# PLT-01-RevC.net
KiCad netlist of a schematic drawn in EAGLE
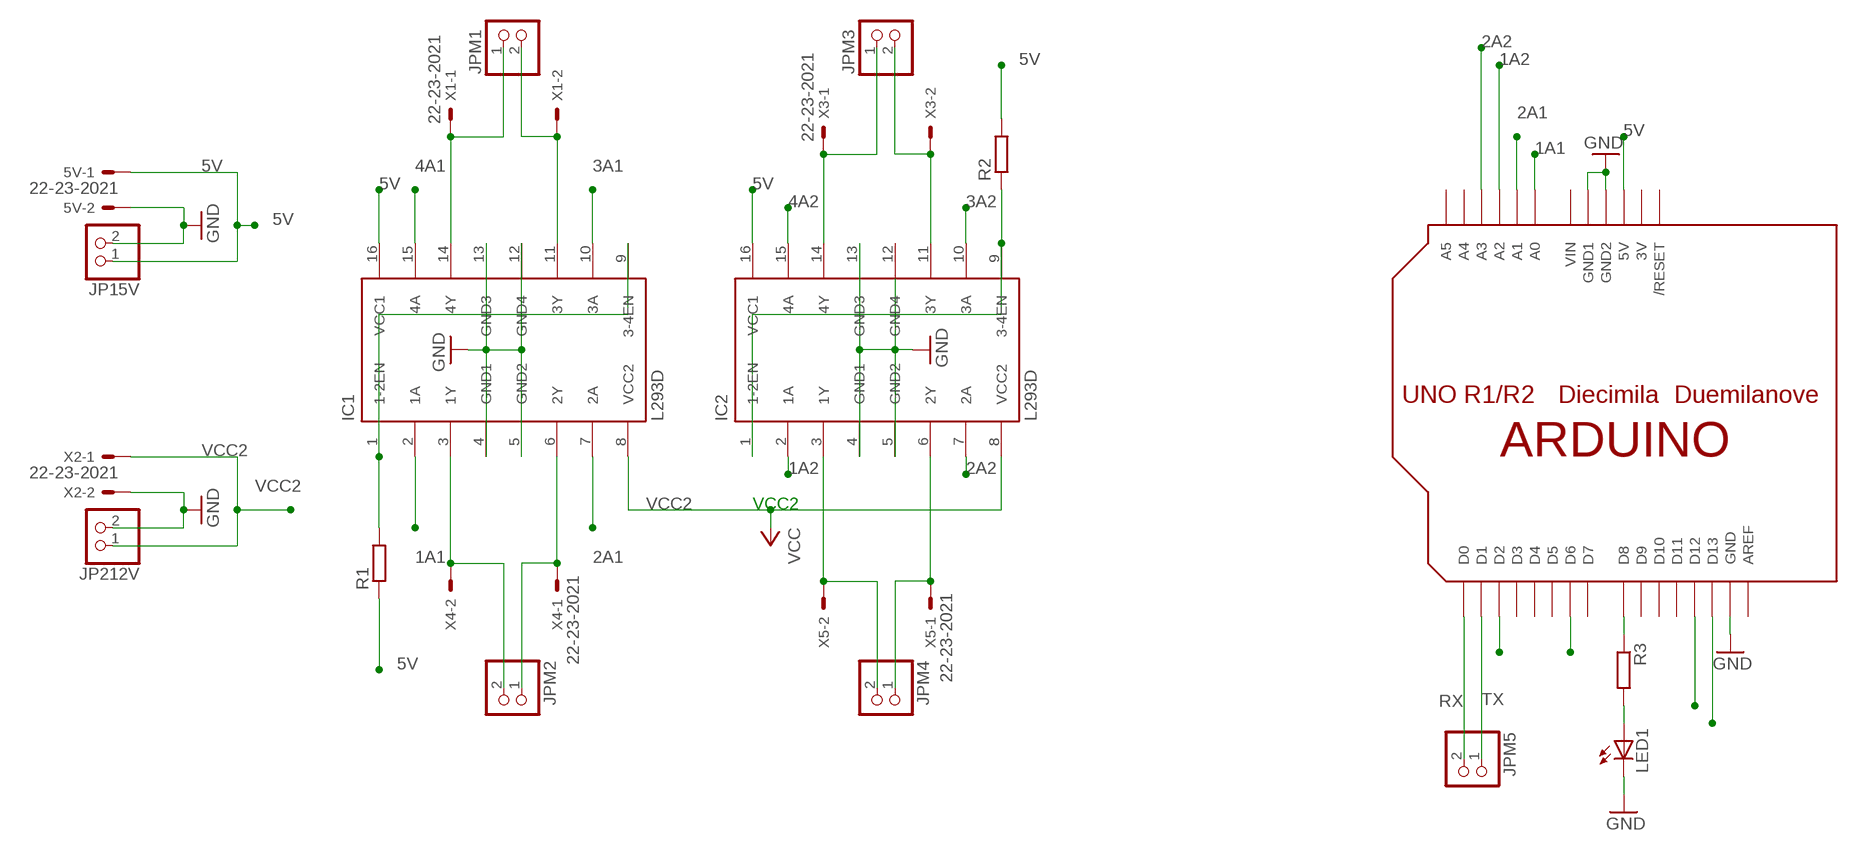
[diagram p0: schematic, sheet 1]

(export (version "E")
  (design (tool "Eeschema 10.0.6"))
  (components
    (comp (ref "5V")
      (value "22-23-2021")
      (footprint "eagle-import:22-23-2021")
      (fields (field (name "MF") "MOLEX"))
      (libsource (lib "eagle-import") (part "22-23-2021"))
    )
    (comp (ref "IC1")
      (value "L293D")
      (footprint "eagle-import:DIL16")
      (libsource (lib "eagle-import") (part "L293D"))
    )
    (comp (ref "IC2")
      (value "L293D")
      (footprint "eagle-import:DIL16")
      (libsource (lib "eagle-import") (part "L293D"))
    )
    (comp (ref "JP15V")
      (value "PINHD-1X2")
      (footprint "eagle-import:1X02")
      (libsource (lib "eagle-import") (part "PINHD-1X2"))
    )
    (comp (ref "JP212V")
      (value "PINHD-1X2")
      (footprint "eagle-import:1X02")
      (libsource (lib "eagle-import") (part "PINHD-1X2"))
    )
    (comp (ref "JPM1")
      (value "PINHD-1X2")
      (footprint "eagle-import:1X02")
      (libsource (lib "eagle-import") (part "PINHD-1X2"))
    )
    (comp (ref "JPM2")
      (value "PINHD-1X2")
      (footprint "eagle-import:1X02")
      (libsource (lib "eagle-import") (part "PINHD-1X2"))
    )
    (comp (ref "JPM3")
      (value "PINHD-1X2")
      (footprint "eagle-import:1X02")
      (libsource (lib "eagle-import") (part "PINHD-1X2"))
    )
    (comp (ref "JPM4")
      (value "PINHD-1X2")
      (footprint "eagle-import:1X02")
      (libsource (lib "eagle-import") (part "PINHD-1X2"))
    )
    (comp (ref "JPM5")
      (value "PINHD-1X2")
      (footprint "eagle-import:1X02")
      (libsource (lib "eagle-import") (part "PINHD-1X2"))
    )
    (comp (ref "LED1")
      (value "LED5MM")
      (footprint "eagle-import:LED5MM")
      (libsource (lib "eagle-import") (part "LED5MM"))
    )
    (comp (ref "R1")
      (value "R-EU_0207/10")
      (footprint "eagle-import:0207_10")
      (libsource (lib "eagle-import") (part "R-EU_0207/10"))
    )
    (comp (ref "R2")
      (value "R-EU_0207/10")
      (footprint "eagle-import:0207_10")
      (libsource (lib "eagle-import") (part "R-EU_0207/10"))
    )
    (comp (ref "R3")
      (value "R-EU_0207/10")
      (footprint "eagle-import:0207_10")
      (libsource (lib "eagle-import") (part "R-EU_0207/10"))
    )
    (comp (ref "U$1")
      (value "ARDUINOUNO")
      (footprint "eagle-import:ARDUINO")
      (libsource (lib "eagle-import") (part "ARDUINOUNO"))
    )
    (comp (ref "X1")
      (value "22-23-2021")
      (footprint "eagle-import:22-23-2021")
      (fields (field (name "MF") "MOLEX"))
      (libsource (lib "eagle-import") (part "22-23-2021"))
    )
    (comp (ref "X2")
      (value "22-23-2021")
      (footprint "eagle-import:22-23-2021")
      (fields (field (name "MF") "MOLEX"))
      (libsource (lib "eagle-import") (part "22-23-2021"))
    )
    (comp (ref "X3")
      (value "22-23-2021")
      (footprint "eagle-import:22-23-2021")
      (fields (field (name "MF") "MOLEX"))
      (libsource (lib "eagle-import") (part "22-23-2021"))
    )
    (comp (ref "X4")
      (value "22-23-2021")
      (footprint "eagle-import:22-23-2021")
      (fields (field (name "MF") "MOLEX"))
      (libsource (lib "eagle-import") (part "22-23-2021"))
    )
    (comp (ref "X5")
      (value "22-23-2021")
      (footprint "eagle-import:22-23-2021")
      (fields (field (name "MF") "MOLEX"))
      (libsource (lib "eagle-import") (part "22-23-2021"))
    )
  )
  (nets
    (net (code "1") (name "/1A1") (class "Default")
      (node (ref "IC1") (pin "2") (pinfunction "1A_2") (pintype "input"))
      (node (ref "U$1") (pin "A0") (pinfunction "A0_A0") (pintype "bidirectional"))
    )
    (net (code "2") (name "/1A2") (class "Default")
      (node (ref "IC2") (pin "2") (pinfunction "1A_2") (pintype "input"))
      (node (ref "U$1") (pin "A2") (pinfunction "A2_A2") (pintype "bidirectional"))
    )
    (net (code "3") (name "/2A1") (class "Default")
      (node (ref "IC1") (pin "7") (pinfunction "2A_7") (pintype "input"))
      (node (ref "U$1") (pin "A1") (pinfunction "A1_A1") (pintype "bidirectional"))
    )
    (net (code "4") (name "/2A2") (class "Default")
      (node (ref "IC2") (pin "7") (pinfunction "2A_7") (pintype "input"))
      (node (ref "U$1") (pin "A3") (pinfunction "A3_A3") (pintype "bidirectional"))
    )
    (net (code "5") (name "/3A1") (class "Default")
      (node (ref "IC1") (pin "10") (pinfunction "3A_10") (pintype "input"))
      (node (ref "U$1") (pin "D12") (pinfunction "D12_D12") (pintype "bidirectional"))
    )
    (net (code "6") (name "/3A2") (class "Default")
      (node (ref "IC2") (pin "10") (pinfunction "3A_10") (pintype "input"))
      (node (ref "U$1") (pin "D2") (pinfunction "D2_D2") (pintype "bidirectional"))
    )
    (net (code "7") (name "/3V") (class "Default")
      (node (ref "U$1") (pin "3V") (pinfunction "3V_3V") (pintype "power_in"))
    )
    (net (code "8") (name "/4A1") (class "Default")
      (node (ref "IC1") (pin "15") (pinfunction "4A_15") (pintype "input"))
      (node (ref "U$1") (pin "D13") (pinfunction "D13_D13") (pintype "bidirectional"))
    )
    (net (code "9") (name "/4A2") (class "Default")
      (node (ref "IC2") (pin "15") (pinfunction "4A_15") (pintype "input"))
      (node (ref "U$1") (pin "D6") (pinfunction "D6_D6") (pintype "bidirectional"))
    )
    (net (code "10") (name "/5V") (class "Default")
      (node (ref "5V") (pin "1") (pinfunction "S_1") (pintype "passive"))
      (node (ref "IC1") (pin "16") (pinfunction "VCC1_16") (pintype "power_in"))
      (node (ref "IC2") (pin "16") (pinfunction "VCC1_16") (pintype "power_in"))
      (node (ref "JP15V") (pin "1") (pinfunction "1_1") (pintype "passive"))
      (node (ref "R1") (pin "1") (pinfunction "1_1") (pintype "passive"))
      (node (ref "R2") (pin "2") (pinfunction "2_2") (pintype "passive"))
      (node (ref "U$1") (pin "5V") (pinfunction "5V_5V") (pintype "power_in"))
    )
    (net (code "11") (name "/GND4") (class "Default")
      (node (ref "IC2") (pin "12") (pinfunction "GND4_12") (pintype "power_in"))
    )
    (net (code "12") (name "/RX") (class "Default")
      (node (ref "JPM5") (pin "2") (pinfunction "2_2") (pintype "passive"))
      (node (ref "U$1") (pin "D0") (pinfunction "D0_D0") (pintype "bidirectional"))
    )
    (net (code "13") (name "/TX") (class "Default")
      (node (ref "JPM5") (pin "1") (pinfunction "1_1") (pintype "passive"))
      (node (ref "U$1") (pin "D1") (pinfunction "D1_D1") (pintype "bidirectional"))
    )
    (net (code "14") (name "/VIN") (class "Default")
      (node (ref "U$1") (pin "VIN") (pinfunction "VIN_VIN") (pintype "power_in"))
    )
    (net (code "15") (name "GND") (class "Default")
      (node (ref "5V") (pin "2") (pinfunction "S_2") (pintype "passive"))
      (node (ref "IC1") (pin "12") (pinfunction "GND4_12") (pintype "power_in"))
      (node (ref "IC1") (pin "13") (pinfunction "GND3_13") (pintype "power_in"))
      (node (ref "IC1") (pin "4") (pinfunction "GND1_4") (pintype "power_in"))
      (node (ref "IC1") (pin "5") (pinfunction "GND2_5") (pintype "power_in"))
      (node (ref "IC2") (pin "13") (pinfunction "GND3_13") (pintype "power_in"))
      (node (ref "IC2") (pin "4") (pinfunction "GND1_4") (pintype "power_in"))
      (node (ref "IC2") (pin "5") (pinfunction "GND2_5") (pintype "power_in"))
      (node (ref "JP15V") (pin "2") (pinfunction "2_2") (pintype "passive"))
      (node (ref "JP212V") (pin "2") (pinfunction "2_2") (pintype "passive"))
      (node (ref "LED1") (pin "K") (pinfunction "C_K") (pintype "passive"))
      (node (ref "U$1") (pin "GND") (pinfunction "GND_GND") (pintype "power_in"))
      (node (ref "U$1") (pin "GND1") (pinfunction "GND1_GND1") (pintype "power_in"))
      (node (ref "U$1") (pin "GND2") (pinfunction "GND2_GND2") (pintype "power_in"))
      (node (ref "X2") (pin "2") (pinfunction "S_2") (pintype "passive"))
    )
    (net (code "16") (name "Net-(IC1-1-2EN)") (class "Default")
      (node (ref "IC1") (pin "1") (pinfunction "1-2EN_1") (pintype "input"))
      (node (ref "IC1") (pin "9") (pinfunction "3-4EN_9") (pintype "input"))
      (node (ref "R1") (pin "2") (pinfunction "2_2") (pintype "passive"))
    )
    (net (code "17") (name "Net-(IC1-1Y)") (class "Default")
      (node (ref "IC1") (pin "3") (pinfunction "1Y_3") (pintype "output"))
      (node (ref "JPM2") (pin "2") (pinfunction "2_2") (pintype "passive"))
      (node (ref "X4") (pin "2") (pinfunction "S_2") (pintype "passive"))
    )
    (net (code "18") (name "Net-(IC1-2Y)") (class "Default")
      (node (ref "IC1") (pin "6") (pinfunction "2Y_6") (pintype "output"))
      (node (ref "JPM2") (pin "1") (pinfunction "1_1") (pintype "passive"))
      (node (ref "X4") (pin "1") (pinfunction "S_1") (pintype "passive"))
    )
    (net (code "19") (name "Net-(IC1-3Y)") (class "Default")
      (node (ref "IC1") (pin "11") (pinfunction "3Y_11") (pintype "output"))
      (node (ref "JPM1") (pin "2") (pinfunction "2_2") (pintype "passive"))
      (node (ref "X1") (pin "2") (pinfunction "S_2") (pintype "passive"))
    )
    (net (code "20") (name "Net-(IC1-4Y)") (class "Default")
      (node (ref "IC1") (pin "14") (pinfunction "4Y_14") (pintype "output"))
      (node (ref "JPM1") (pin "1") (pinfunction "1_1") (pintype "passive"))
      (node (ref "X1") (pin "1") (pinfunction "S_1") (pintype "passive"))
    )
    (net (code "21") (name "Net-(IC2-1-2EN)") (class "Default")
      (node (ref "IC2") (pin "1") (pinfunction "1-2EN_1") (pintype "input"))
      (node (ref "IC2") (pin "9") (pinfunction "3-4EN_9") (pintype "input"))
      (node (ref "R2") (pin "1") (pinfunction "1_1") (pintype "passive"))
    )
    (net (code "22") (name "Net-(IC2-1Y)") (class "Default")
      (node (ref "IC2") (pin "3") (pinfunction "1Y_3") (pintype "output"))
      (node (ref "JPM4") (pin "2") (pinfunction "2_2") (pintype "passive"))
      (node (ref "X5") (pin "2") (pinfunction "S_2") (pintype "passive"))
    )
    (net (code "23") (name "Net-(IC2-2Y)") (class "Default")
      (node (ref "IC2") (pin "6") (pinfunction "2Y_6") (pintype "output"))
      (node (ref "JPM4") (pin "1") (pinfunction "1_1") (pintype "passive"))
      (node (ref "X5") (pin "1") (pinfunction "S_1") (pintype "passive"))
    )
    (net (code "24") (name "Net-(IC2-3Y)") (class "Default")
      (node (ref "IC2") (pin "11") (pinfunction "3Y_11") (pintype "output"))
      (node (ref "JPM3") (pin "2") (pinfunction "2_2") (pintype "passive"))
      (node (ref "X3") (pin "2") (pinfunction "S_2") (pintype "passive"))
    )
    (net (code "25") (name "Net-(IC2-4Y)") (class "Default")
      (node (ref "IC2") (pin "14") (pinfunction "4Y_14") (pintype "output"))
      (node (ref "JPM3") (pin "1") (pinfunction "1_1") (pintype "passive"))
      (node (ref "X3") (pin "1") (pinfunction "S_1") (pintype "passive"))
    )
    (net (code "26") (name "Net-(LED1-PadA)") (class "Default")
      (node (ref "LED1") (pin "A") (pinfunction "A_A") (pintype "passive"))
      (node (ref "R3") (pin "2") (pinfunction "2_2") (pintype "passive"))
    )
    (net (code "27") (name "Net-(R3-Pad1)") (class "Default")
      (node (ref "R3") (pin "1") (pinfunction "1_1") (pintype "passive"))
      (node (ref "U$1") (pin "D8") (pinfunction "D8_D8") (pintype "bidirectional"))
    )
    (net (code "28") (name "VCC") (class "Default")
      (node (ref "IC1") (pin "8") (pinfunction "VCC2_8") (pintype "power_in"))
      (node (ref "IC2") (pin "8") (pinfunction "VCC2_8") (pintype "power_in"))
      (node (ref "JP212V") (pin "1") (pinfunction "1_1") (pintype "passive"))
      (node (ref "X2") (pin "1") (pinfunction "S_1") (pintype "passive"))
    )
    (net (code "29") (name "unconnected-(U$1-PadA4)") (class "Default")
      (node (ref "U$1") (pin "A4") (pinfunction "A4_A4") (pintype "bidirectional"))
    )
    (net (code "30") (name "unconnected-(U$1-PadA5)") (class "Default")
      (node (ref "U$1") (pin "A5") (pinfunction "A5_A5") (pintype "bidirectional"))
    )
    (net (code "31") (name "unconnected-(U$1-PadAREF)") (class "Default")
      (node (ref "U$1") (pin "AREF") (pinfunction "AREF_AREF") (pintype "bidirectional"))
    )
    (net (code "32") (name "unconnected-(U$1-PadD3)") (class "Default")
      (node (ref "U$1") (pin "D3") (pinfunction "D3_D3") (pintype "bidirectional"))
    )
    (net (code "33") (name "unconnected-(U$1-PadD4)") (class "Default")
      (node (ref "U$1") (pin "D4") (pinfunction "D4_D4") (pintype "bidirectional"))
    )
    (net (code "34") (name "unconnected-(U$1-PadD5)") (class "Default")
      (node (ref "U$1") (pin "D5") (pinfunction "D5_D5") (pintype "bidirectional"))
    )
    (net (code "35") (name "unconnected-(U$1-PadD7)") (class "Default")
      (node (ref "U$1") (pin "D7") (pinfunction "D7_D7") (pintype "bidirectional"))
    )
    (net (code "36") (name "unconnected-(U$1-PadD9)") (class "Default")
      (node (ref "U$1") (pin "D9") (pinfunction "D9_D9") (pintype "bidirectional"))
    )
    (net (code "37") (name "unconnected-(U$1-PadD10)") (class "Default")
      (node (ref "U$1") (pin "D10") (pinfunction "D10_D10") (pintype "bidirectional"))
    )
    (net (code "38") (name "unconnected-(U$1-PadD11)") (class "Default")
      (node (ref "U$1") (pin "D11") (pinfunction "D11_D11") (pintype "bidirectional"))
    )
    (net (code "39") (name "unconnected-(U$1-{slash}RESET-PadRESET)") (class "Default")
      (node (ref "U$1") (pin "RESET") (pinfunction "/RESET_RESET") (pintype "bidirectional"))
    )
  )
)
